# clvHd_EMG.net
KiCad netlist of a schematic drawn in EAGLE
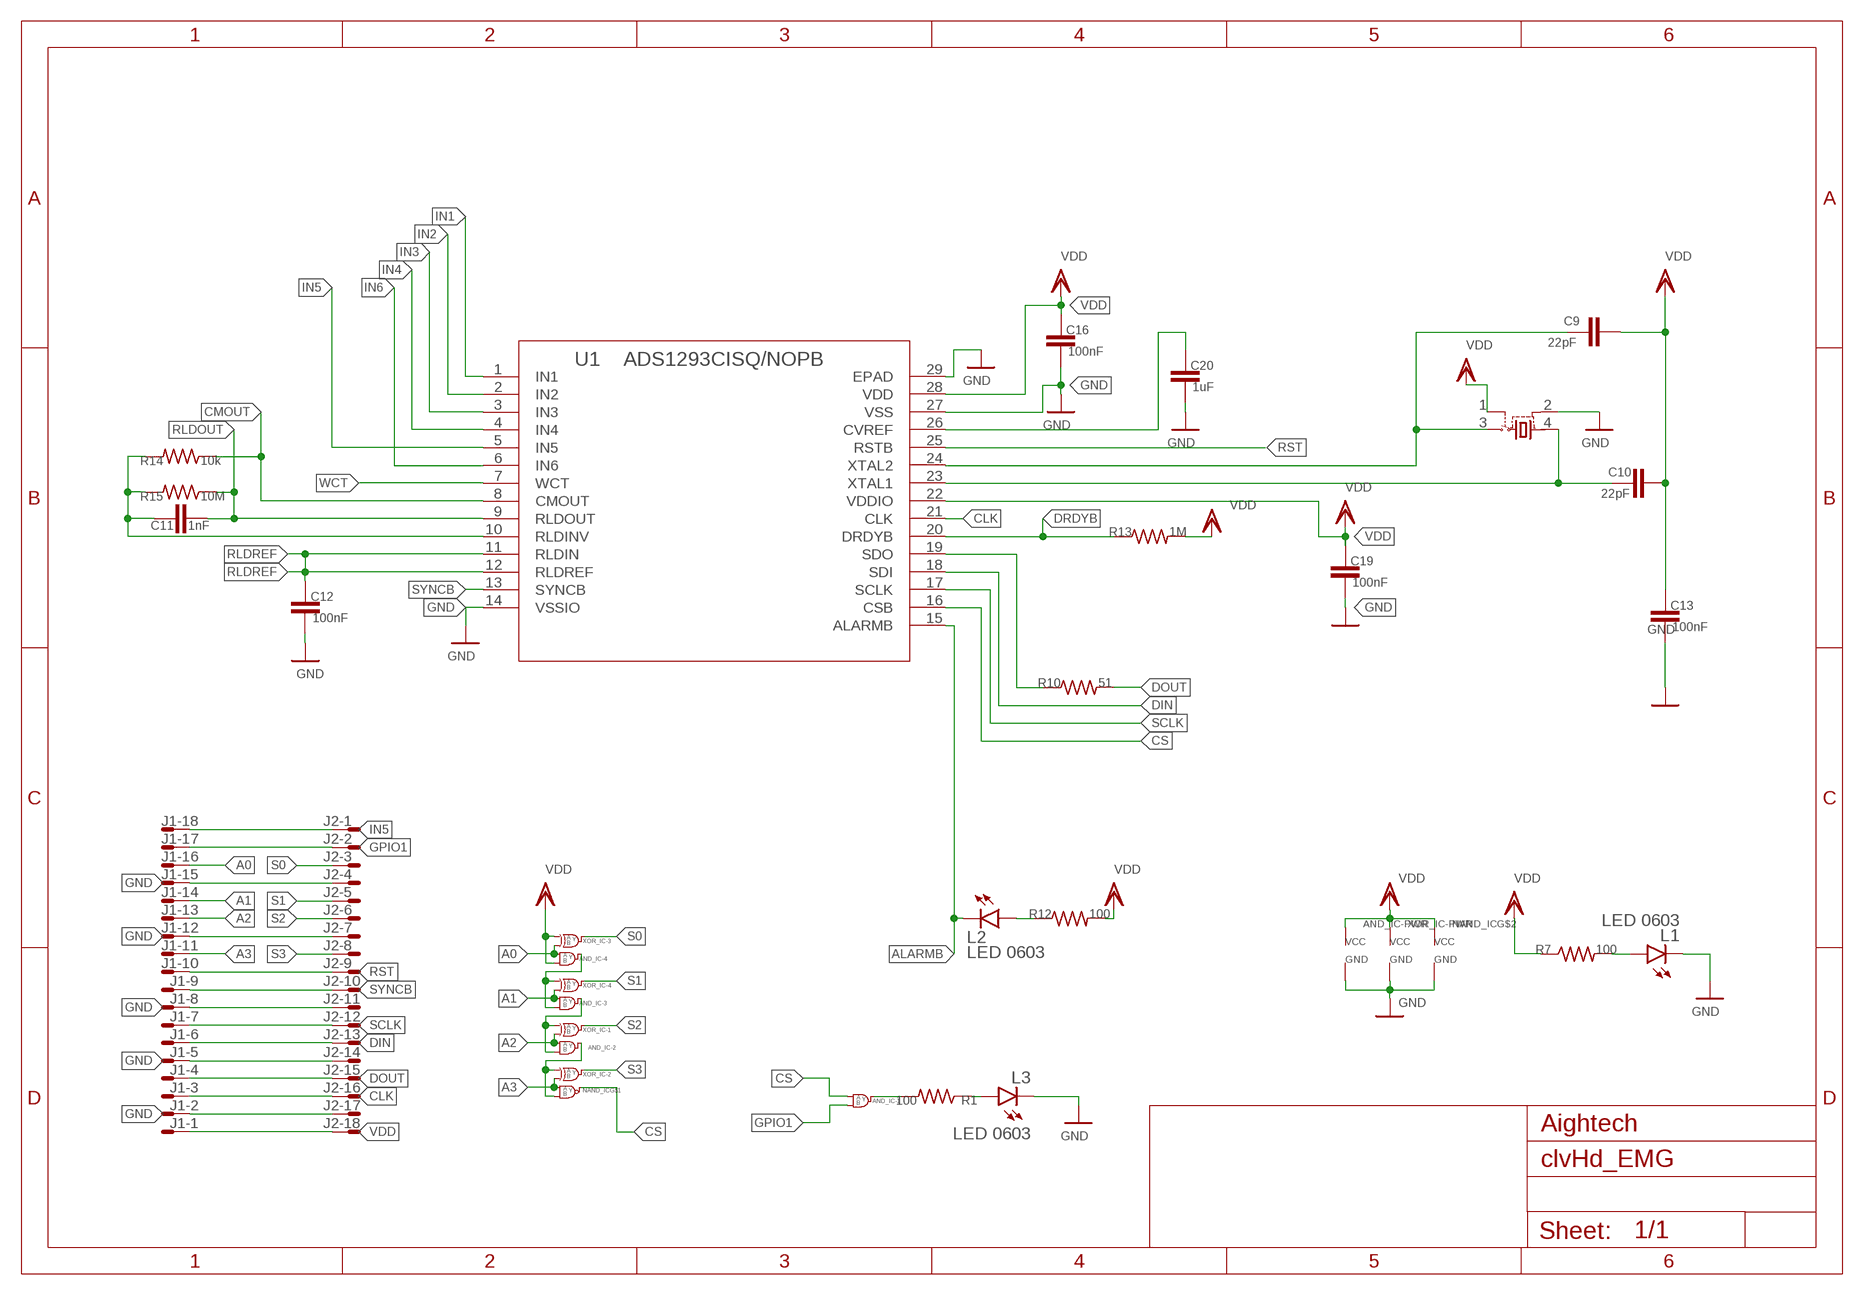
[diagram p0: schematic, sheet 1]

(export (version "E")
  (design (tool "Eeschema 10.0.6"))
  (components
    (comp (ref "AND_IC")
      (value "SN74ALVC08LARGE")
      (footprint "eagle-import:SN74LVC86ARGYR")
      (libsource (lib "eagle-import") (part "SN74ALVC08LARGE"))
    )
    (comp (ref "C9")
      (value "22pF")
      (footprint "eagle-import:C0402")
      (libsource (lib "eagle-import") (part "C-EUC0402"))
    )
    (comp (ref "C10")
      (value "22pF")
      (footprint "eagle-import:C0402")
      (libsource (lib "eagle-import") (part "C-EUC0402"))
    )
    (comp (ref "C11")
      (value "1nF")
      (footprint "eagle-import:C0402")
      (libsource (lib "eagle-import") (part "C-EUC0402"))
    )
    (comp (ref "C12")
      (value "100nF")
      (footprint "eagle-import:C0402")
      (libsource (lib "eagle-import") (part "C-EUC0402"))
    )
    (comp (ref "C13")
      (value "100nF")
      (footprint "eagle-import:C0402")
      (libsource (lib "eagle-import") (part "C-EUC0402"))
    )
    (comp (ref "C16")
      (value "100nF")
      (footprint "eagle-import:C0402")
      (libsource (lib "eagle-import") (part "C-EUC0402"))
    )
    (comp (ref "C19")
      (value "100nF")
      (footprint "eagle-import:C0402")
      (libsource (lib "eagle-import") (part "C-EUC0402"))
    )
    (comp (ref "C20")
      (value "1uF")
      (footprint "eagle-import:C0402")
      (libsource (lib "eagle-import") (part "C-EUC0402"))
    )
    (comp (ref "J1")
      (value "XF2J-1824-12")
      (footprint "eagle-import:XF2J-1824-12")
      (libsource (lib "eagle-import") (part "XF2-18?24-12J"))
    )
    (comp (ref "J2")
      (value "XF2J-1824-12")
      (footprint "eagle-import:XF2J-1824-12")
      (libsource (lib "eagle-import") (part "XF2-18?24-12J"))
    )
    (comp (ref "L1")
      (value "LED 0603")
      (footprint "eagle-import:CHIP-LED0603")
      (libsource (lib "eagle-import") (part "LEDCHIP-LED0603"))
    )
    (comp (ref "L2")
      (value "LED 0603")
      (footprint "eagle-import:CHIP-LED0603")
      (libsource (lib "eagle-import") (part "LEDCHIP-LED0603"))
    )
    (comp (ref "L3")
      (value "LED 0603")
      (footprint "eagle-import:CHIP-LED0603")
      (libsource (lib "eagle-import") (part "LEDCHIP-LED0603"))
    )
    (comp (ref "NAND_IC")
      (value "SN74LVC1G132DCKT")
      (footprint "eagle-import:SOT65P210X110-5N")
      (libsource (lib "eagle-import") (part "SN74LVC1G132DCKT"))
    )
    (comp (ref "R1")
      (value "100")
      (footprint "eagle-import:R0402")
      (libsource (lib "eagle-import") (part "rcl_334_R-US_R0402"))
    )
    (comp (ref "R7")
      (value "100")
      (footprint "eagle-import:R0402")
      (libsource (lib "eagle-import") (part "rcl_334_R-US_R0402"))
    )
    (comp (ref "R10")
      (value "51")
      (footprint "eagle-import:R0402")
      (libsource (lib "eagle-import") (part "rcl_334_R-US_R0402"))
    )
    (comp (ref "R12")
      (value "100")
      (footprint "eagle-import:R0402")
      (libsource (lib "eagle-import") (part "rcl_334_R-US_R0402"))
    )
    (comp (ref "R13")
      (value "1M")
      (footprint "eagle-import:R0402")
      (libsource (lib "eagle-import") (part "R-US_R0402"))
    )
    (comp (ref "R14")
      (value "10k")
      (footprint "eagle-import:R0402")
      (libsource (lib "eagle-import") (part "rcl_334_R-US_R0402"))
    )
    (comp (ref "R15")
      (value "10M")
      (footprint "eagle-import:R0402")
      (libsource (lib "eagle-import") (part "rcl_334_R-US_R0402"))
    )
    (comp (ref "U$1")
      (value "C387328")
      (footprint "eagle-import:SMD-3225_4P")
      (libsource (lib "eagle-import") (part "C387328"))
    )
    (comp (ref "U1")
      (value "ADS1293CISQ/NOPB")
      (footprint "eagle-import:RSG28_3P6X3P6_TEX")
      (libsource (lib "eagle-import") (part "ADS1293CISQ/NOPB"))
    )
    (comp (ref "XOR_IC")
      (value "SN74LVC86A")
      (footprint "eagle-import:SN74LVC86ARGYR")
      (libsource (lib "eagle-import") (part "SN74LVC86A"))
    )
  )
  (nets
    (net (code "1") (name "A0") (class "Default")
      (node (ref "AND_IC") (pin "12") (pinfunction "A_12") (pintype "input"))
      (node (ref "J1") (pin "16") (pinfunction "MS_16") (pintype "passive"))
      (node (ref "XOR_IC") (pin "10") (pinfunction "B_10") (pintype "input"))
    )
    (net (code "2") (name "A1") (class "Default")
      (node (ref "AND_IC") (pin "9") (pinfunction "A_9") (pintype "input"))
      (node (ref "J1") (pin "14") (pinfunction "MS_14") (pintype "passive"))
      (node (ref "XOR_IC") (pin "13") (pinfunction "B_13") (pintype "input"))
    )
    (net (code "3") (name "A2") (class "Default")
      (node (ref "AND_IC") (pin "4") (pinfunction "A_4") (pintype "input"))
      (node (ref "J1") (pin "13") (pinfunction "MS_13") (pintype "passive"))
      (node (ref "XOR_IC") (pin "2") (pinfunction "B_2") (pintype "input"))
    )
    (net (code "4") (name "A3") (class "Default")
      (node (ref "J1") (pin "11") (pinfunction "MS_11") (pintype "passive"))
      (node (ref "NAND_IC") (pin "1") (pinfunction "A_1") (pintype "input"))
      (node (ref "XOR_IC") (pin "5") (pinfunction "B_5") (pintype "input"))
    )
    (net (code "5") (name "ALARMB") (class "Default")
      (node (ref "L2") (pin "C") (pinfunction "C_C") (pintype "passive"))
      (node (ref "U1") (pin "15") (pinfunction "ALARMB_15") (pintype "output"))
    )
    (net (code "6") (name "CLK") (class "Default")
      (node (ref "J1") (pin "3") (pinfunction "MS_3") (pintype "passive"))
      (node (ref "J2") (pin "16") (pinfunction "MS_16") (pintype "passive"))
      (node (ref "U1") (pin "21") (pinfunction "CLK_21") (pintype "bidirectional"))
    )
    (net (code "7") (name "CMOUT") (class "Default")
      (node (ref "R14") (pin "1") (pinfunction "1_1") (pintype "passive"))
      (node (ref "U1") (pin "8") (pinfunction "CMOUT_8") (pintype "output"))
    )
    (net (code "8") (name "CS") (class "Default")
      (node (ref "AND_IC") (pin "1") (pinfunction "A_1") (pintype "input"))
      (node (ref "NAND_IC") (pin "4") (pinfunction "Y_4") (pintype "output"))
      (node (ref "U1") (pin "16") (pinfunction "CSB_16") (pintype "input"))
    )
    (net (code "9") (name "DIN") (class "Default")
      (node (ref "J1") (pin "6") (pinfunction "MS_6") (pintype "passive"))
      (node (ref "J2") (pin "13") (pinfunction "MS_13") (pintype "passive"))
      (node (ref "U1") (pin "18") (pinfunction "SDI_18") (pintype "input"))
    )
    (net (code "10") (name "DOUT") (class "Default")
      (node (ref "J1") (pin "4") (pinfunction "MS_4") (pintype "passive"))
      (node (ref "J2") (pin "15") (pinfunction "MS_15") (pintype "passive"))
      (node (ref "R10") (pin "2") (pinfunction "2_2") (pintype "passive"))
    )
    (net (code "11") (name "DRDYB") (class "Default")
      (node (ref "R13") (pin "1") (pinfunction "1_1") (pintype "passive"))
      (node (ref "U1") (pin "20") (pinfunction "DRDYB_20") (pintype "output"))
    )
    (net (code "12") (name "GND") (class "Default")
      (node (ref "AND_IC") (pin "15") (pinfunction "GND_15") (pintype "power_in"))
      (node (ref "AND_IC") (pin "7") (pinfunction "GND_7") (pintype "power_in"))
      (node (ref "C12") (pin "2") (pinfunction "2_2") (pintype "passive"))
      (node (ref "C13") (pin "2") (pinfunction "2_2") (pintype "passive"))
      (node (ref "C16") (pin "2") (pinfunction "2_2") (pintype "passive"))
      (node (ref "C19") (pin "2") (pinfunction "2_2") (pintype "passive"))
      (node (ref "C20") (pin "2") (pinfunction "2_2") (pintype "passive"))
      (node (ref "J1") (pin "12") (pinfunction "MS_12") (pintype "passive"))
      (node (ref "J1") (pin "15") (pinfunction "MS_15") (pintype "passive"))
      (node (ref "J1") (pin "2") (pinfunction "MS_2") (pintype "passive"))
      (node (ref "J1") (pin "5") (pinfunction "MS_5") (pintype "passive"))
      (node (ref "J1") (pin "8") (pinfunction "MS_8") (pintype "passive"))
      (node (ref "J2") (pin "11") (pinfunction "MS_11") (pintype "passive"))
      (node (ref "J2") (pin "14") (pinfunction "MS_14") (pintype "passive"))
      (node (ref "J2") (pin "17") (pinfunction "MS_17") (pintype "passive"))
      (node (ref "J2") (pin "4") (pinfunction "MS_4") (pintype "passive"))
      (node (ref "J2") (pin "7") (pinfunction "MS_7") (pintype "passive"))
      (node (ref "L1") (pin "C") (pinfunction "C_C") (pintype "passive"))
      (node (ref "L3") (pin "C") (pinfunction "C_C") (pintype "passive"))
      (node (ref "NAND_IC") (pin "3") (pinfunction "GND_3") (pintype "power_in"))
      (node (ref "U$1") (pin "2") (pinfunction "GND_2") (pintype "power_in"))
      (node (ref "U1") (pin "14") (pinfunction "VSSIO_14") (pintype "power_in"))
      (node (ref "U1") (pin "27") (pinfunction "VSS_27") (pintype "power_in"))
      (node (ref "U1") (pin "29") (pinfunction "EPAD_29") (pintype "passive"))
      (node (ref "XOR_IC") (pin "15") (pinfunction "GND_15") (pintype "power_in"))
      (node (ref "XOR_IC") (pin "7") (pinfunction "GND_7") (pintype "power_in"))
    )
    (net (code "13") (name "GPIO1") (class "Default")
      (node (ref "AND_IC") (pin "2") (pinfunction "B_2") (pintype "input"))
      (node (ref "J1") (pin "17") (pinfunction "MS_17") (pintype "passive"))
      (node (ref "J2") (pin "2") (pinfunction "MS_2") (pintype "passive"))
    )
    (net (code "14") (name "IN1") (class "Default")
      (node (ref "U1") (pin "1") (pinfunction "IN1_1") (pintype "input"))
    )
    (net (code "15") (name "IN2") (class "Default")
      (node (ref "U1") (pin "2") (pinfunction "IN2_2") (pintype "input"))
    )
    (net (code "16") (name "IN3") (class "Default")
      (node (ref "U1") (pin "3") (pinfunction "IN3_3") (pintype "input"))
    )
    (net (code "17") (name "IN4") (class "Default")
      (node (ref "U1") (pin "4") (pinfunction "IN4_4") (pintype "input"))
    )
    (net (code "18") (name "IN5") (class "Default")
      (node (ref "J1") (pin "18") (pinfunction "MS_18") (pintype "passive"))
      (node (ref "J2") (pin "1") (pinfunction "MSV_1") (pintype "passive"))
      (node (ref "U1") (pin "5") (pinfunction "IN5_5") (pintype "input"))
    )
    (net (code "19") (name "IN6") (class "Default")
      (node (ref "U1") (pin "6") (pinfunction "IN6_6") (pintype "input"))
    )
    (net (code "20") (name "Net-(AND_ICA-Y)") (class "Default")
      (node (ref "AND_IC") (pin "3") (pinfunction "Y_3") (pintype "output"))
      (node (ref "R1") (pin "2") (pinfunction "2_2") (pintype "passive"))
    )
    (net (code "21") (name "Net-(AND_ICB-B)") (class "Default")
      (node (ref "AND_IC") (pin "5") (pinfunction "B_5") (pintype "input"))
      (node (ref "AND_IC") (pin "8") (pinfunction "Y_8") (pintype "output"))
      (node (ref "XOR_IC") (pin "1") (pinfunction "A_1") (pintype "input"))
    )
    (net (code "22") (name "Net-(AND_ICB-Y)") (class "Default")
      (node (ref "AND_IC") (pin "6") (pinfunction "Y_6") (pintype "output"))
      (node (ref "NAND_IC") (pin "2") (pinfunction "B_2") (pintype "input"))
      (node (ref "XOR_IC") (pin "4") (pinfunction "A_4") (pintype "input"))
    )
    (net (code "23") (name "Net-(AND_ICC-B)") (class "Default")
      (node (ref "AND_IC") (pin "10") (pinfunction "B_10") (pintype "input"))
      (node (ref "AND_IC") (pin "11") (pinfunction "Y_11") (pintype "output"))
      (node (ref "XOR_IC") (pin "12") (pinfunction "A_12") (pintype "input"))
    )
    (net (code "24") (name "Net-(L1-PadA)") (class "Default")
      (node (ref "L1") (pin "A") (pinfunction "A_A") (pintype "passive"))
      (node (ref "R7") (pin "2") (pinfunction "2_2") (pintype "passive"))
    )
    (net (code "25") (name "Net-(L2-PadA)") (class "Default")
      (node (ref "L2") (pin "A") (pinfunction "A_A") (pintype "passive"))
      (node (ref "R12") (pin "1") (pinfunction "1_1") (pintype "passive"))
    )
    (net (code "26") (name "Net-(L3-PadA)") (class "Default")
      (node (ref "L3") (pin "A") (pinfunction "A_A") (pintype "passive"))
      (node (ref "R1") (pin "1") (pinfunction "1_1") (pintype "passive"))
    )
    (net (code "27") (name "Net-(U$1-OUT)") (class "Default")
      (node (ref "C9") (pin "2") (pinfunction "2_2") (pintype "passive"))
      (node (ref "U$1") (pin "3") (pinfunction "OUT_3") (pintype "output"))
      (node (ref "U1") (pin "24") (pinfunction "XTAL2_24") (pintype "input"))
    )
    (net (code "28") (name "Net-(U$1-VDD)") (class "Default")
      (node (ref "C10") (pin "2") (pinfunction "2_2") (pintype "passive"))
      (node (ref "U$1") (pin "4") (pinfunction "VDD_4") (pintype "power_in"))
      (node (ref "U1") (pin "23") (pinfunction "XTAL1_23") (pintype "input"))
    )
    (net (code "29") (name "Net-(U1-CVREF)") (class "Default")
      (node (ref "C20") (pin "1") (pinfunction "1_1") (pintype "passive"))
      (node (ref "U1") (pin "26") (pinfunction "CVREF_26") (pintype "bidirectional"))
    )
    (net (code "30") (name "Net-(U1-RLDINV)") (class "Default")
      (node (ref "C11") (pin "1") (pinfunction "1_1") (pintype "passive"))
      (node (ref "R14") (pin "2") (pinfunction "2_2") (pintype "passive"))
      (node (ref "R15") (pin "2") (pinfunction "2_2") (pintype "passive"))
      (node (ref "U1") (pin "10") (pinfunction "RLDINV_10") (pintype "input"))
    )
    (net (code "31") (name "Net-(U1-SDO)") (class "Default")
      (node (ref "R10") (pin "1") (pinfunction "1_1") (pintype "passive"))
      (node (ref "U1") (pin "19") (pinfunction "SDO_19") (pintype "output"))
    )
    (net (code "32") (name "RLDOUT") (class "Default")
      (node (ref "C11") (pin "2") (pinfunction "2_2") (pintype "passive"))
      (node (ref "R15") (pin "1") (pinfunction "1_1") (pintype "passive"))
      (node (ref "U1") (pin "9") (pinfunction "RLDOUT_9") (pintype "output"))
    )
    (net (code "33") (name "RLDREF") (class "Default")
      (node (ref "C12") (pin "1") (pinfunction "1_1") (pintype "passive"))
      (node (ref "U1") (pin "11") (pinfunction "RLDIN_11") (pintype "bidirectional"))
      (node (ref "U1") (pin "12") (pinfunction "RLDREF_12") (pintype "output"))
    )
    (net (code "34") (name "RST") (class "Default")
      (node (ref "J1") (pin "10") (pinfunction "MS_10") (pintype "passive"))
      (node (ref "J2") (pin "9") (pinfunction "MS_9") (pintype "passive"))
      (node (ref "U1") (pin "25") (pinfunction "RSTB_25") (pintype "input"))
    )
    (net (code "35") (name "S0") (class "Default")
      (node (ref "J2") (pin "3") (pinfunction "MS_3") (pintype "passive"))
      (node (ref "XOR_IC") (pin "8") (pinfunction "Y_8") (pintype "output"))
    )
    (net (code "36") (name "S1") (class "Default")
      (node (ref "J2") (pin "5") (pinfunction "MS_5") (pintype "passive"))
      (node (ref "XOR_IC") (pin "11") (pinfunction "Y_11") (pintype "output"))
    )
    (net (code "37") (name "S2") (class "Default")
      (node (ref "J2") (pin "6") (pinfunction "MS_6") (pintype "passive"))
      (node (ref "XOR_IC") (pin "3") (pinfunction "Y_3") (pintype "output"))
    )
    (net (code "38") (name "S3") (class "Default")
      (node (ref "J2") (pin "8") (pinfunction "MS_8") (pintype "passive"))
      (node (ref "XOR_IC") (pin "6") (pinfunction "Y_6") (pintype "output"))
    )
    (net (code "39") (name "SCLK") (class "Default")
      (node (ref "J1") (pin "7") (pinfunction "MS_7") (pintype "passive"))
      (node (ref "J2") (pin "12") (pinfunction "MS_12") (pintype "passive"))
      (node (ref "U1") (pin "17") (pinfunction "SCLK_17") (pintype "input"))
    )
    (net (code "40") (name "SYNCB") (class "Default")
      (node (ref "J1") (pin "9") (pinfunction "MS_9") (pintype "passive"))
      (node (ref "J2") (pin "10") (pinfunction "MS_10") (pintype "passive"))
      (node (ref "U1") (pin "13") (pinfunction "SYNCB_13") (pintype "bidirectional"))
    )
    (net (code "41") (name "VDD") (class "Default")
      (node (ref "AND_IC") (pin "13") (pinfunction "B_13") (pintype "input"))
      (node (ref "AND_IC") (pin "14") (pinfunction "VCC_14") (pintype "power_in"))
      (node (ref "C10") (pin "1") (pinfunction "1_1") (pintype "passive"))
      (node (ref "C13") (pin "1") (pinfunction "1_1") (pintype "passive"))
      (node (ref "C16") (pin "1") (pinfunction "1_1") (pintype "passive"))
      (node (ref "C19") (pin "1") (pinfunction "1_1") (pintype "passive"))
      (node (ref "C9") (pin "1") (pinfunction "1_1") (pintype "passive"))
      (node (ref "J1") (pin "1") (pinfunction "MSV_1") (pintype "passive"))
      (node (ref "J2") (pin "18") (pinfunction "MS_18") (pintype "passive"))
      (node (ref "NAND_IC") (pin "5") (pinfunction "VCC_5") (pintype "power_in"))
      (node (ref "R12") (pin "2") (pinfunction "2_2") (pintype "passive"))
      (node (ref "R13") (pin "2") (pinfunction "2_2") (pintype "passive"))
      (node (ref "R7") (pin "1") (pinfunction "1_1") (pintype "passive"))
      (node (ref "U$1") (pin "1") (pinfunction "TRI_1") (pintype "input"))
      (node (ref "U1") (pin "22") (pinfunction "VDDIO_22") (pintype "power_in"))
      (node (ref "U1") (pin "28") (pinfunction "VDD_28") (pintype "power_in"))
      (node (ref "XOR_IC") (pin "14") (pinfunction "VCC_14") (pintype "power_in"))
      (node (ref "XOR_IC") (pin "9") (pinfunction "A_9") (pintype "input"))
    )
    (net (code "42") (name "WCT") (class "Default")
      (node (ref "U1") (pin "7") (pinfunction "WCT_7") (pintype "output"))
    )
  )
)
